# MCU_Board_fNIRS_POWER.net
KiCad netlist of a schematic drawn in Altium Designer
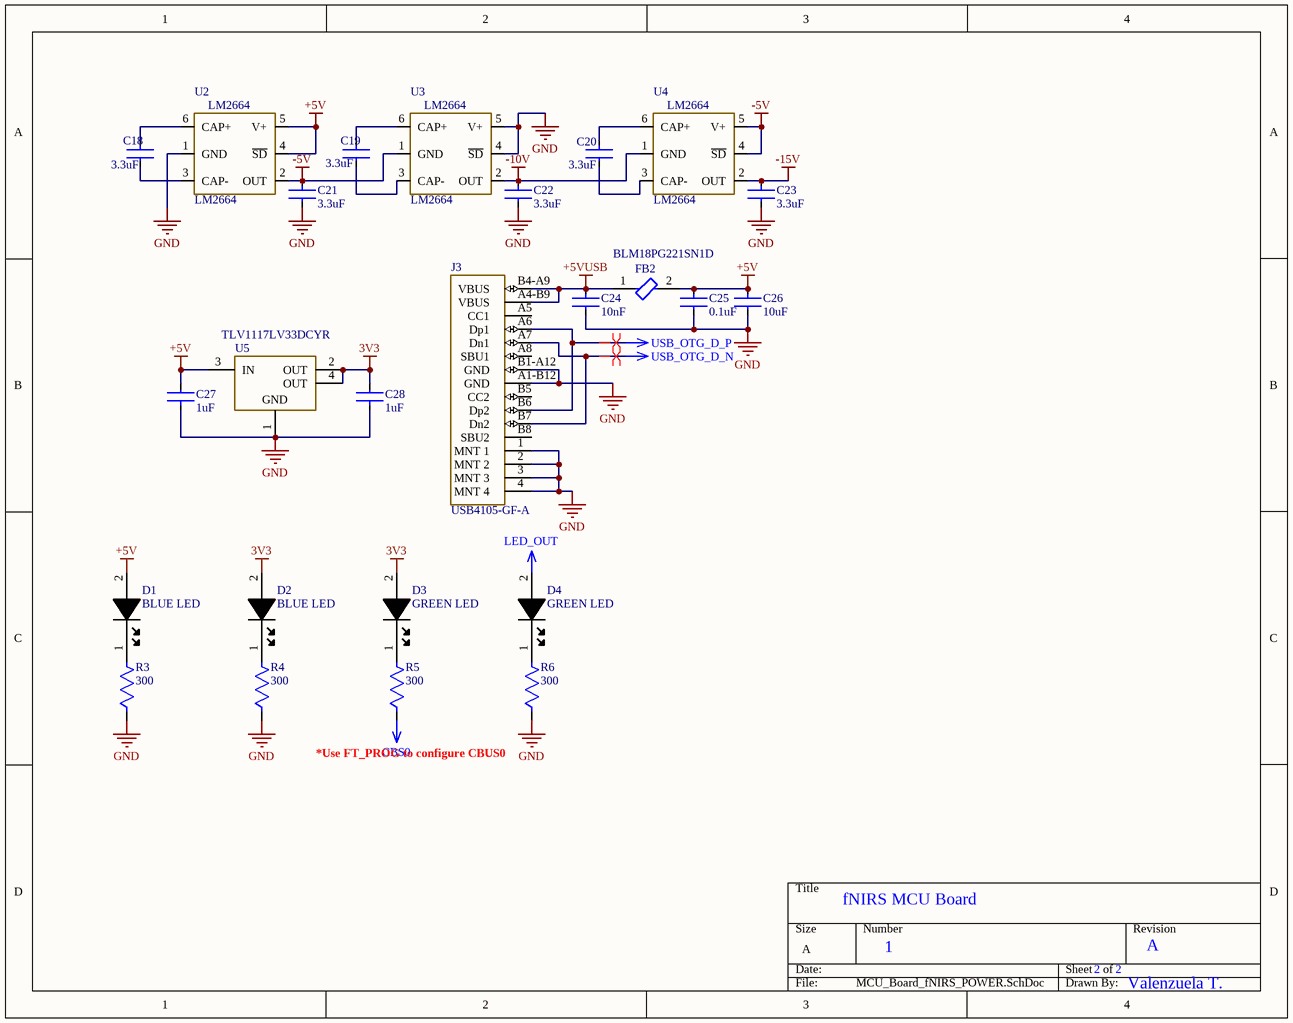
[diagram p0: MCU_Board_fNIRS_POWER.SchDoc]

(export (version "E")
  (design (tool "Eeschema 10.0.6"))
  (components
    (comp (ref "C18")
      (value "3.3uF")
      (footprint "CAPC1210(3225)190_M")
      (description "1210")
      (libsource (lib "Single_Channel_fNIRS") (part "C1210C335K5RAC7800"))
    )
    (comp (ref "C19")
      (value "3.3uF")
      (footprint "CAPC1210(3225)190_M")
      (description "1210")
      (libsource (lib "Single_Channel_fNIRS") (part "C1210C335K5RAC7800"))
    )
    (comp (ref "C20")
      (value "3.3uF")
      (footprint "CAPC1210(3225)190_M")
      (description "1210")
      (libsource (lib "Single_Channel_fNIRS") (part "C1210C335K5RAC7800"))
    )
    (comp (ref "C21")
      (value "3.3uF")
      (footprint "CAPC1210(3225)190_M")
      (description "1210")
      (libsource (lib "Single_Channel_fNIRS") (part "C1210C335K5RAC7800"))
    )
    (comp (ref "C22")
      (value "3.3uF")
      (footprint "CAPC1210(3225)190_M")
      (description "1210")
      (libsource (lib "Single_Channel_fNIRS") (part "C1210C335K5RAC7800"))
    )
    (comp (ref "C23")
      (value "3.3uF")
      (footprint "CAPC1210(3225)190_M")
      (description "1210")
      (libsource (lib "Single_Channel_fNIRS") (part "C1210C335K5RAC7800"))
    )
    (comp (ref "C24")
      (value "10nF")
      (footprint "CAPC1206(3216)130_M")
      (description "10000 pF ±10% 63V Ceramic Capacitor X7R 1206 (3216 Metric)")
      (fields (field (name "TOLERANCE") "-20% to +80%"))
      (libsource (lib "MCU_Board_fNIRS") (part "C1206C103KMREC7800"))
    )
    (comp (ref "C25")
      (value "0.1uF")
      (footprint "CAPC3216X180N")
      (description "1206")
      (fields (field (name "TOLERANCE") "0.1") (field (name "MANUFACTURER") "KEMET"))
      (libsource (lib "Single_Channel_fNIRS") (part "C1206C104K5RAC7210"))
    )
    (comp (ref "C26")
      (value "10uF")
      (footprint "CAPC3216X180N")
      (description "1206")
      (libsource (lib "Single_Channel_fNIRS") (part "CL31B106KOHNNWE"))
    )
    (comp (ref "C27")
      (value "1uF")
      (footprint "CAPC3216X180N")
      (description "CAP 1uF 25V -20% to +80% 1206 (3216 Metric) Thickness 1.3mm")
      (fields (field (name "TOLERANCE") "-20% to +80%"))
      (libsource (lib "MCU_Board_fNIRS") (part "12063G105ZAT4A"))
    )
    (comp (ref "C28")
      (value "1uF")
      (footprint "CAPC3216X180N")
      (description "CAP 1uF 25V -20% to +80% 1206 (3216 Metric) Thickness 1.3mm")
      (fields (field (name "TOLERANCE") "-20% to +80%"))
      (libsource (lib "MCU_Board_fNIRS") (part "12063G105ZAT4A"))
    )
    (comp (ref "D1")
      (value "BLUE LED")
      (footprint "XZCFBB54W-1VF")
      (description "Blue 470nm LED Indication - Discrete 2.65V 0805 (2012 Metric)")
      (libsource (lib "MCU_Board_fNIRS") (part "XZCFBB54W-1VF"))
    )
    (comp (ref "D2")
      (value "BLUE LED")
      (footprint "XZCFBB54W-1VF")
      (description "Blue 470nm LED Indication - Discrete 2.65V 0805 (2012 Metric)")
      (libsource (lib "MCU_Board_fNIRS") (part "XZCFBB54W-1VF"))
    )
    (comp (ref "D3")
      (value "GREEN LED")
      (footprint "XZCFBB54W-1VF")
      (description "Green 525nm LED Indication - Discrete 2.65V 0805 (2012 Metric)")
      (libsource (lib "MCU_Board_fNIRS") (part "XZCDGK54W-1VF"))
    )
    (comp (ref "D4")
      (value "GREEN LED")
      (footprint "XZCFBB54W-1VF")
      (description "Green 525nm LED Indication - Discrete 2.65V 0805 (2012 Metric)")
      (libsource (lib "MCU_Board_fNIRS") (part "XZCDGK54W-1VF"))
    )
    (comp (ref "FB2")
      (value "BLM18PG221SN1D")
      (footprint "BEADC1608X95N")
      (description "220 Ohms @ 100 MHz 1 Power Line Ferrite Bead 0603 (1608 Metric) 1.4A 100mOhm")
      (fields (field (name "TOLERANCE") "-20% to +80%"))
      (libsource (lib "MCU_Board_fNIRS") (part "BLM18PG221SN1D"))
    )
    (comp (ref "J3")
      (value "USB4105-GF-A")
      (footprint "FP-USB4105-GF-A-MFG")
      (description "CONN RCPT USB2.0 TYPEC 5A")
      (fields
        (field (name "MANUFACTURER") "GCT")
        (field (name "OCTOPART") "https://octopart.com/usb4105-gf-a-gct-106627878")
      )
      (libsource (lib "MCU_Board_fNIRS") (part "USB4105-GF-A"))
    )
    (comp (ref "R3")
      (value "300")
      (footprint "R1206")
      (description "300 Ohms ±1% 0.25W, 1/4W Chip Resistor 1206 (3216 Metric) Automotive AEC-Q200 Thick Film")
      (libsource (lib "MCU_Board_fNIRS") (part "CRCW1206300RFKEA"))
    )
    (comp (ref "R4")
      (value "300")
      (footprint "R1206")
      (description "300 Ohms ±1% 0.25W, 1/4W Chip Resistor 1206 (3216 Metric) Automotive AEC-Q200 Thick Film")
      (libsource (lib "MCU_Board_fNIRS") (part "CRCW1206300RFKEA"))
    )
    (comp (ref "R5")
      (value "300")
      (footprint "R1206")
      (description "CRCW1206300RFKEA")
      (libsource (lib "MCU_Board_fNIRS") (part "CRCW1206300RFKEA"))
    )
    (comp (ref "R6")
      (value "300")
      (footprint "R1206")
      (description "300 Ohms ±1% 0.25W, 1/4W Chip Resistor 1206 (3216 Metric) Automotive AEC-Q200 Thick Film")
      (libsource (lib "MCU_Board_fNIRS") (part "CRCW1206300RFKEA"))
    )
    (comp (ref "U2")
      (value "LM2664")
      (footprint "LM2664")
      (description "Switched Capacitor Voltage Converter, 6-pin SOT-23")
      (fields (field (name "MANUFACTURER") "Texas Instruments"))
      (libsource (lib "Single_Channel_fNIRS") (part "LM2664"))
    )
    (comp (ref "U3")
      (value "LM2664")
      (footprint "LM2664")
      (description "Switched Capacitor Voltage Converter, 6-pin SOT-23")
      (fields (field (name "MANUFACTURER") "Texas Instruments"))
      (libsource (lib "Single_Channel_fNIRS") (part "LM2664"))
    )
    (comp (ref "U4")
      (value "LM2664")
      (footprint "LM2664")
      (description "Switched Capacitor Voltage Converter, 6-pin SOT-23")
      (fields (field (name "MANUFACTURER") "Texas Instruments"))
      (libsource (lib "Single_Channel_fNIRS") (part "LM2664"))
    )
    (comp (ref "U5")
      (value "TLV1117LV33DCYR")
      (footprint "DCY0004A_M")
      (fields (field (name "MANUFACTURER") "Texas Instruments"))
      (libsource (lib "MCU_Board_fNIRS") (part "CMP-0395-00503-2"))
    )
  )
  (nets
    (net (code "1") (name "+5V") (class "Default")
      (node (ref "C25") (pin "1") (pinfunction "1_1") (pintype "passive"))
      (node (ref "C26") (pin "1") (pinfunction "1_1") (pintype "passive"))
      (node (ref "C27") (pin "2") (pinfunction "2_2") (pintype "passive"))
      (node (ref "D1") (pin "2") (pinfunction "2_2") (pintype "passive"))
      (node (ref "FB2") (pin "2") (pinfunction "2_2") (pintype "passive"))
      (node (ref "U2") (pin "4") (pinfunction "~{SD}_4") (pintype "passive"))
      (node (ref "U2") (pin "5") (pinfunction "V+_5") (pintype "passive"))
      (node (ref "U5") (pin "3") (pinfunction "IN_3") (pintype "power_in"))
    )
    (net (code "2") (name "+5VUSB") (class "Default")
      (node (ref "C24") (pin "1") (pinfunction "1_1") (pintype "passive"))
      (node (ref "FB2") (pin "1") (pinfunction "1_1") (pintype "passive"))
      (node (ref "J3") (pin "A4-B9") (pinfunction "VBUS_A4-B9") (pintype "power_in"))
      (node (ref "J3") (pin "B4-A9") (pinfunction "VBUS_B4-A9") (pintype "bidirectional"))
    )
    (net (code "3") (name "-5V") (class "Default")
      (node (ref "C21") (pin "1") (pinfunction "1_1") (pintype "passive"))
      (node (ref "U2") (pin "2") (pinfunction "OUT_2") (pintype "passive"))
      (node (ref "U3") (pin "1") (pinfunction "GND_1") (pintype "passive"))
      (node (ref "U4") (pin "4") (pinfunction "~{SD}_4") (pintype "passive"))
      (node (ref "U4") (pin "5") (pinfunction "V+_5") (pintype "passive"))
    )
    (net (code "4") (name "-10V") (class "Default")
      (node (ref "C22") (pin "1") (pinfunction "1_1") (pintype "passive"))
      (node (ref "U3") (pin "2") (pinfunction "OUT_2") (pintype "passive"))
      (node (ref "U4") (pin "1") (pinfunction "GND_1") (pintype "passive"))
    )
    (net (code "5") (name "-15V") (class "Default")
      (node (ref "C23") (pin "1") (pinfunction "1_1") (pintype "passive"))
      (node (ref "U4") (pin "2") (pinfunction "OUT_2") (pintype "passive"))
    )
    (net (code "6") (name "3V3") (class "Default")
      (node (ref "C28") (pin "2") (pinfunction "2_2") (pintype "passive"))
      (node (ref "D2") (pin "2") (pinfunction "2_2") (pintype "passive"))
      (node (ref "D3") (pin "2") (pinfunction "2_2") (pintype "passive"))
      (node (ref "U5") (pin "2") (pinfunction "OUT_2") (pintype "power_in"))
      (node (ref "U5") (pin "4") (pinfunction "OUT_4") (pintype "power_in"))
    )
    (net (code "7") (name "CBS0") (class "Default")
      (node (ref "R5") (pin "1") (pinfunction "1_1") (pintype "passive"))
    )
    (net (code "8") (name "GND") (class "Default")
      (node (ref "C21") (pin "2") (pinfunction "2_2") (pintype "passive"))
      (node (ref "C22") (pin "2") (pinfunction "2_2") (pintype "passive"))
      (node (ref "C23") (pin "2") (pinfunction "2_2") (pintype "passive"))
      (node (ref "C24") (pin "2") (pinfunction "2_2") (pintype "passive"))
      (node (ref "C25") (pin "2") (pinfunction "2_2") (pintype "passive"))
      (node (ref "C26") (pin "2") (pinfunction "2_2") (pintype "passive"))
      (node (ref "C27") (pin "1") (pinfunction "1_1") (pintype "passive"))
      (node (ref "C28") (pin "1") (pinfunction "1_1") (pintype "passive"))
      (node (ref "J3") (pin "1") (pinfunction "MNT_1_1") (pintype "power_in"))
      (node (ref "J3") (pin "2") (pinfunction "MNT_2_2") (pintype "power_in"))
      (node (ref "J3") (pin "3") (pinfunction "MNT_3_3") (pintype "power_in"))
      (node (ref "J3") (pin "4") (pinfunction "MNT_4_4") (pintype "power_in"))
      (node (ref "J3") (pin "A1-B12") (pinfunction "GND_A1-B12") (pintype "power_in"))
      (node (ref "J3") (pin "B1-A12") (pinfunction "GND_B1-A12") (pintype "bidirectional"))
      (node (ref "R3") (pin "1") (pinfunction "1_1") (pintype "passive"))
      (node (ref "R4") (pin "1") (pinfunction "1_1") (pintype "passive"))
      (node (ref "R6") (pin "1") (pinfunction "1_1") (pintype "passive"))
      (node (ref "U2") (pin "1") (pinfunction "GND_1") (pintype "passive"))
      (node (ref "U3") (pin "4") (pinfunction "~{SD}_4") (pintype "passive"))
      (node (ref "U3") (pin "5") (pinfunction "V+_5") (pintype "passive"))
      (node (ref "U5") (pin "1") (pinfunction "GND_1") (pintype "power_in"))
    )
    (net (code "9") (name "LED_OUT") (class "Default")
      (node (ref "D4") (pin "2") (pinfunction "2_2") (pintype "passive"))
    )
    (net (code "10") (name "Net-(D1-Pad1)") (class "Default")
      (node (ref "D1") (pin "1") (pinfunction "1_1") (pintype "passive"))
      (node (ref "R3") (pin "2") (pinfunction "2_2") (pintype "passive"))
    )
    (net (code "11") (name "Net-(D2-Pad1)") (class "Default")
      (node (ref "D2") (pin "1") (pinfunction "1_1") (pintype "passive"))
      (node (ref "R4") (pin "2") (pinfunction "2_2") (pintype "passive"))
    )
    (net (code "12") (name "Net-(D3-Pad1)") (class "Default")
      (node (ref "D3") (pin "1") (pinfunction "1_1") (pintype "passive"))
      (node (ref "R5") (pin "2") (pinfunction "2_2") (pintype "passive"))
    )
    (net (code "13") (name "Net-(D4-Pad1)") (class "Default")
      (node (ref "D4") (pin "1") (pinfunction "1_1") (pintype "passive"))
      (node (ref "R6") (pin "2") (pinfunction "2_2") (pintype "passive"))
    )
    (net (code "14") (name "Net-(U2-CAP+)") (class "Default")
      (node (ref "C18") (pin "1") (pinfunction "1_1") (pintype "passive"))
      (node (ref "U2") (pin "6") (pinfunction "CAP+_6") (pintype "passive"))
    )
    (net (code "15") (name "Net-(U2-CAP-)") (class "Default")
      (node (ref "C18") (pin "2") (pinfunction "2_2") (pintype "passive"))
      (node (ref "U2") (pin "3") (pinfunction "CAP-_3") (pintype "passive"))
    )
    (net (code "16") (name "Net-(U3-CAP+)") (class "Default")
      (node (ref "C19") (pin "1") (pinfunction "1_1") (pintype "passive"))
      (node (ref "U3") (pin "6") (pinfunction "CAP+_6") (pintype "passive"))
    )
    (net (code "17") (name "Net-(U3-CAP-)") (class "Default")
      (node (ref "C19") (pin "2") (pinfunction "2_2") (pintype "passive"))
      (node (ref "U3") (pin "3") (pinfunction "CAP-_3") (pintype "passive"))
    )
    (net (code "18") (name "Net-(U4-CAP+)") (class "Default")
      (node (ref "C20") (pin "1") (pinfunction "1_1") (pintype "passive"))
      (node (ref "U4") (pin "6") (pinfunction "CAP+_6") (pintype "passive"))
    )
    (net (code "19") (name "Net-(U4-CAP-)") (class "Default")
      (node (ref "C20") (pin "2") (pinfunction "2_2") (pintype "passive"))
      (node (ref "U4") (pin "3") (pinfunction "CAP-_3") (pintype "passive"))
    )
    (net (code "20") (name "USB_OTG_D_N") (class "Default")
      (node (ref "J3") (pin "A7") (pinfunction "Dn1_A7") (pintype "bidirectional"))
      (node (ref "J3") (pin "B7") (pinfunction "Dn2_B7") (pintype "bidirectional"))
    )
    (net (code "21") (name "USB_OTG_D_P") (class "Default")
      (node (ref "J3") (pin "A6") (pinfunction "Dp1_A6") (pintype "bidirectional"))
      (node (ref "J3") (pin "B6") (pinfunction "Dp2_B6") (pintype "bidirectional"))
    )
    (net (code "22") (name "unconnected-(J3-CC1-PadA5)") (class "Default")
      (node (ref "J3") (pin "A5") (pinfunction "CC1_A5") (pintype "power_in"))
    )
    (net (code "23") (name "unconnected-(J3-CC2-PadB5)") (class "Default")
      (node (ref "J3") (pin "B5") (pinfunction "CC2_B5") (pintype "bidirectional"))
    )
    (net (code "24") (name "unconnected-(J3-SBU1-PadA8)") (class "Default")
      (node (ref "J3") (pin "A8") (pinfunction "SBU1_A8") (pintype "bidirectional"))
    )
    (net (code "25") (name "unconnected-(J3-SBU2-PadB8)") (class "Default")
      (node (ref "J3") (pin "B8") (pinfunction "SBU2_B8") (pintype "power_in"))
    )
  )
)
